# mcb.net
KiCad netlist of a schematic drawn in EAGLE
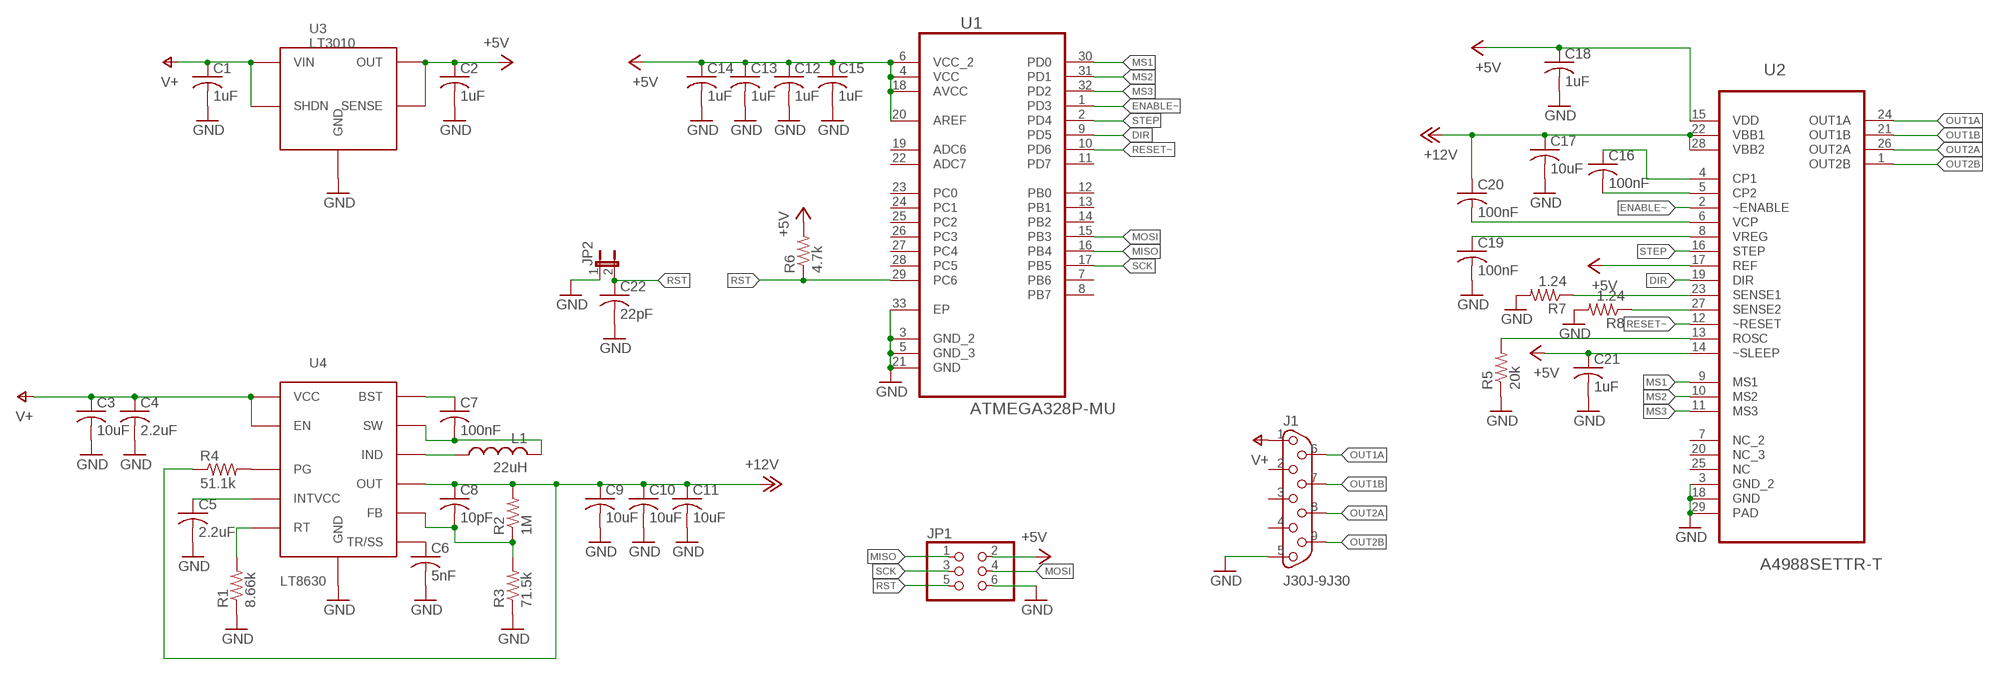
[diagram p0: schematic, sheet 1]

(export (version "E")
  (design (tool "Eeschema 10.0.6"))
  (components
    (comp (ref "C1")
      (value "1uF")
      (footprint "eagle-import:C0603")
      (libsource (lib "eagle-import") (part "C-USC0603"))
    )
    (comp (ref "C2")
      (value "1uF")
      (footprint "eagle-import:C0603")
      (libsource (lib "eagle-import") (part "C-USC0603"))
    )
    (comp (ref "C3")
      (value "10uF")
      (footprint "eagle-import:C1206")
      (libsource (lib "eagle-import") (part "C-USC1206"))
    )
    (comp (ref "C4")
      (value "2.2uF")
      (footprint "eagle-import:C0805")
      (libsource (lib "eagle-import") (part "C-USC0805"))
    )
    (comp (ref "C5")
      (value "2.2uF")
      (footprint "eagle-import:C0805")
      (libsource (lib "eagle-import") (part "C-USC0805"))
    )
    (comp (ref "C6")
      (value "5nF")
      (footprint "eagle-import:C0603")
      (libsource (lib "eagle-import") (part "C-USC0603"))
    )
    (comp (ref "C7")
      (value "100nF")
      (footprint "eagle-import:C0603")
      (libsource (lib "eagle-import") (part "C-USC0603"))
    )
    (comp (ref "C8")
      (value "10pF")
      (footprint "eagle-import:C0603")
      (libsource (lib "eagle-import") (part "C-USC0603"))
    )
    (comp (ref "C9")
      (value "10uF")
      (footprint "eagle-import:C1206")
      (libsource (lib "eagle-import") (part "C-USC1206"))
    )
    (comp (ref "C10")
      (value "10uF")
      (footprint "eagle-import:C1206")
      (libsource (lib "eagle-import") (part "C-USC1206"))
    )
    (comp (ref "C11")
      (value "10uF")
      (footprint "eagle-import:C1206")
      (libsource (lib "eagle-import") (part "C-USC1206"))
    )
    (comp (ref "C12")
      (value "1uF")
      (footprint "eagle-import:C0603")
      (libsource (lib "eagle-import") (part "C-USC0603"))
    )
    (comp (ref "C13")
      (value "1uF")
      (footprint "eagle-import:C0603")
      (libsource (lib "eagle-import") (part "C-USC0603"))
    )
    (comp (ref "C14")
      (value "1uF")
      (footprint "eagle-import:C0603")
      (libsource (lib "eagle-import") (part "C-USC0603"))
    )
    (comp (ref "C15")
      (value "1uF")
      (footprint "eagle-import:C0603")
      (libsource (lib "eagle-import") (part "C-USC0603"))
    )
    (comp (ref "C16")
      (value "100nF")
      (footprint "eagle-import:C0603")
      (libsource (lib "eagle-import") (part "C-USC0603"))
    )
    (comp (ref "C17")
      (value "10uF")
      (footprint "eagle-import:C1206")
      (libsource (lib "eagle-import") (part "C-USC1206"))
    )
    (comp (ref "C18")
      (value "1uF")
      (footprint "eagle-import:C0603")
      (libsource (lib "eagle-import") (part "C-USC0603"))
    )
    (comp (ref "C19")
      (value "100nF")
      (footprint "eagle-import:C0603")
      (libsource (lib "eagle-import") (part "C-USC0603"))
    )
    (comp (ref "C20")
      (value "100nF")
      (footprint "eagle-import:C0603")
      (libsource (lib "eagle-import") (part "C-USC0603"))
    )
    (comp (ref "C21")
      (value "1uF")
      (footprint "eagle-import:C0603")
      (libsource (lib "eagle-import") (part "C-USC0603"))
    )
    (comp (ref "C22")
      (value "22pF")
      (footprint "eagle-import:C0603")
      (libsource (lib "eagle-import") (part "C-USC0603"))
    )
    (comp (ref "J1")
      (value "J30J-9J30")
      (footprint "eagle-import:ZKN-9-J30")
      (libsource (lib "eagle-import") (part "J30J-9J30"))
    )
    (comp (ref "JP1")
      (value "PINHD-2X3")
      (footprint "eagle-import:2X03")
      (libsource (lib "eagle-import") (part "PINHD-2X3"))
    )
    (comp (ref "JP2")
      (value "JUMPER-2SMD-NO")
      (footprint "eagle-import:SJ_2S-NO")
      (libsource (lib "eagle-import") (part "JUMPER-2SMD-NO"))
    )
    (comp (ref "L1")
      (value "22uH")
      (footprint "eagle-import:SRP1265A")
      (libsource (lib "eagle-import") (part "INDUCTOR"))
    )
    (comp (ref "R1")
      (value "8.66k")
      (footprint "eagle-import:R0603")
      (libsource (lib "eagle-import") (part "R-US_R0603"))
    )
    (comp (ref "R2")
      (value "1M")
      (footprint "eagle-import:R0603")
      (libsource (lib "eagle-import") (part "R-US_R0603"))
    )
    (comp (ref "R3")
      (value "71.5k")
      (footprint "eagle-import:R0603")
      (libsource (lib "eagle-import") (part "R-US_R0603"))
    )
    (comp (ref "R4")
      (value "51.1k")
      (footprint "eagle-import:R0603")
      (libsource (lib "eagle-import") (part "R-US_R0603"))
    )
    (comp (ref "R5")
      (value "20k")
      (footprint "eagle-import:R0603")
      (libsource (lib "eagle-import") (part "R-US_R0603"))
    )
    (comp (ref "R6")
      (value "4.7k")
      (footprint "eagle-import:R0603")
      (libsource (lib "eagle-import") (part "R-US_R0603"))
    )
    (comp (ref "R7")
      (value "1.24")
      (footprint "eagle-import:R0603")
      (libsource (lib "eagle-import") (part "R-US_R0603"))
    )
    (comp (ref "R8")
      (value "1.24")
      (footprint "eagle-import:R0603")
      (libsource (lib "eagle-import") (part "R-US_R0603"))
    )
    (comp (ref "U1")
      (value "ATMEGA328P-MU")
      (footprint "eagle-import:QFN50P500X500X100-33N")
      (libsource (lib "eagle-import") (part "ATMEGA328P-MU"))
    )
    (comp (ref "U2")
      (value "A4988SETTR-T")
      (footprint "eagle-import:QFN50P500X500X100-29N")
      (libsource (lib "eagle-import") (part "A4988SETTR-T"))
    )
    (comp (ref "U3")
      (value "LT3010")
      (footprint "eagle-import:8-MSOP")
      (libsource (lib "eagle-import") (part "LT3010"))
    )
    (comp (ref "U4")
      (value "LT8630")
      (footprint "eagle-import:20-TSSOP")
      (libsource (lib "eagle-import") (part "LT8630"))
    )
  )
  (nets
    (net (code "1") (name "+5V") (class "Default")
      (node (ref "C12") (pin "1") (pinfunction "1_1") (pintype "passive"))
      (node (ref "C13") (pin "1") (pinfunction "1_1") (pintype "passive"))
      (node (ref "C14") (pin "1") (pinfunction "1_1") (pintype "passive"))
      (node (ref "C15") (pin "1") (pinfunction "1_1") (pintype "passive"))
      (node (ref "C18") (pin "1") (pinfunction "1_1") (pintype "passive"))
      (node (ref "C2") (pin "1") (pinfunction "1_1") (pintype "passive"))
      (node (ref "C21") (pin "1") (pinfunction "1_1") (pintype "passive"))
      (node (ref "JP1") (pin "2") (pinfunction "2_2") (pintype "passive"))
      (node (ref "R6") (pin "2") (pinfunction "2_2") (pintype "passive"))
      (node (ref "U1") (pin "18") (pinfunction "AVCC_18") (pintype "power_in"))
      (node (ref "U1") (pin "20") (pinfunction "AREF_20") (pintype "input"))
      (node (ref "U1") (pin "4") (pinfunction "VCC_4") (pintype "power_in"))
      (node (ref "U1") (pin "6") (pinfunction "VCC_2_6") (pintype "power_in"))
      (node (ref "U2") (pin "14") (pinfunction "~{SLEEP}_14") (pintype "input"))
      (node (ref "U2") (pin "15") (pinfunction "VDD_15") (pintype "power_in"))
      (node (ref "U2") (pin "17") (pinfunction "REF_17") (pintype "input"))
      (node (ref "U3") (pin "1") (pinfunction "OUT_1") (pintype "bidirectional"))
      (node (ref "U3") (pin "2") (pinfunction "SENSE_2") (pintype "bidirectional"))
    )
    (net (code "2") (name "+12V") (class "Default")
      (node (ref "C10") (pin "1") (pinfunction "1_1") (pintype "passive"))
      (node (ref "C11") (pin "1") (pinfunction "1_1") (pintype "passive"))
      (node (ref "C17") (pin "1") (pinfunction "1_1") (pintype "passive"))
      (node (ref "C20") (pin "1") (pinfunction "1_1") (pintype "passive"))
      (node (ref "C8") (pin "1") (pinfunction "1_1") (pintype "passive"))
      (node (ref "C9") (pin "1") (pinfunction "1_1") (pintype "passive"))
      (node (ref "R2") (pin "2") (pinfunction "2_2") (pintype "passive"))
      (node (ref "R4") (pin "1") (pinfunction "1_1") (pintype "passive"))
      (node (ref "U2") (pin "22") (pinfunction "VBB1_22") (pintype "power_in"))
      (node (ref "U2") (pin "28") (pinfunction "VBB2_28") (pintype "power_in"))
      (node (ref "U4") (pin "P$12") (pinfunction "OUT_P$12") (pintype "bidirectional"))
    )
    (net (code "3") (name "/ENABLE~{}") (class "Default")
      (node (ref "U1") (pin "1") (pinfunction "PD3_1") (pintype "bidirectional"))
      (node (ref "U2") (pin "2") (pinfunction "~{ENABLE}_2") (pintype "input"))
    )
    (net (code "4") (name "/RESET~{}") (class "Default")
      (node (ref "U1") (pin "10") (pinfunction "PD6_10") (pintype "bidirectional"))
      (node (ref "U2") (pin "12") (pinfunction "~{RESET}_12") (pintype "input"))
    )
    (net (code "5") (name "DIR") (class "Default")
      (node (ref "U1") (pin "9") (pinfunction "PD5_9") (pintype "bidirectional"))
      (node (ref "U2") (pin "19") (pinfunction "DIR_19") (pintype "input"))
    )
    (net (code "6") (name "GND") (class "Default")
      (node (ref "C1") (pin "2") (pinfunction "2_2") (pintype "passive"))
      (node (ref "C10") (pin "2") (pinfunction "2_2") (pintype "passive"))
      (node (ref "C11") (pin "2") (pinfunction "2_2") (pintype "passive"))
      (node (ref "C12") (pin "2") (pinfunction "2_2") (pintype "passive"))
      (node (ref "C13") (pin "2") (pinfunction "2_2") (pintype "passive"))
      (node (ref "C14") (pin "2") (pinfunction "2_2") (pintype "passive"))
      (node (ref "C15") (pin "2") (pinfunction "2_2") (pintype "passive"))
      (node (ref "C17") (pin "2") (pinfunction "2_2") (pintype "passive"))
      (node (ref "C18") (pin "2") (pinfunction "2_2") (pintype "passive"))
      (node (ref "C19") (pin "2") (pinfunction "2_2") (pintype "passive"))
      (node (ref "C2") (pin "2") (pinfunction "2_2") (pintype "passive"))
      (node (ref "C21") (pin "2") (pinfunction "2_2") (pintype "passive"))
      (node (ref "C22") (pin "2") (pinfunction "2_2") (pintype "passive"))
      (node (ref "C3") (pin "2") (pinfunction "2_2") (pintype "passive"))
      (node (ref "C4") (pin "2") (pinfunction "2_2") (pintype "passive"))
      (node (ref "C5") (pin "2") (pinfunction "2_2") (pintype "passive"))
      (node (ref "C6") (pin "2") (pinfunction "2_2") (pintype "passive"))
      (node (ref "C9") (pin "2") (pinfunction "2_2") (pintype "passive"))
      (node (ref "J1") (pin "5") (pinfunction "5_5") (pintype "bidirectional"))
      (node (ref "JP1") (pin "6") (pinfunction "6_6") (pintype "passive"))
      (node (ref "JP2") (pin "1") (pinfunction "1_1") (pintype "passive"))
      (node (ref "R1") (pin "1") (pinfunction "1_1") (pintype "passive"))
      (node (ref "R3") (pin "1") (pinfunction "1_1") (pintype "passive"))
      (node (ref "R5") (pin "1") (pinfunction "1_1") (pintype "passive"))
      (node (ref "R7") (pin "2") (pinfunction "2_2") (pintype "passive"))
      (node (ref "R8") (pin "2") (pinfunction "2_2") (pintype "passive"))
      (node (ref "U1") (pin "21") (pinfunction "GND_21") (pintype "passive"))
      (node (ref "U1") (pin "3") (pinfunction "GND_2_3") (pintype "passive"))
      (node (ref "U1") (pin "33") (pinfunction "EP_33") (pintype "passive"))
      (node (ref "U1") (pin "5") (pinfunction "GND_3_5") (pintype "passive"))
      (node (ref "U2") (pin "18") (pinfunction "GND_18") (pintype "passive"))
      (node (ref "U2") (pin "29") (pinfunction "PAD_29") (pintype "passive"))
      (node (ref "U2") (pin "3") (pinfunction "GND_2_3") (pintype "passive"))
      (node (ref "U3") (pin "3") (pinfunction "GND_3") (pintype "bidirectional"))
      (node (ref "U3") (pin "4") (pinfunction "GND_4") (pintype "bidirectional"))
      (node (ref "U3") (pin "6") (pinfunction "GND_6") (pintype "bidirectional"))
      (node (ref "U3") (pin "7") (pinfunction "GND_7") (pintype "bidirectional"))
      (node (ref "U3") (pin "9") (pinfunction "GND_9") (pintype "bidirectional"))
      (node (ref "U4") (pin "P$0") (pinfunction "GND_P$0") (pintype "bidirectional"))
    )
    (net (code "7") (name "MISO") (class "Default")
      (node (ref "JP1") (pin "1") (pinfunction "1_1") (pintype "passive"))
      (node (ref "U1") (pin "16") (pinfunction "PB4_16") (pintype "bidirectional"))
    )
    (net (code "8") (name "MOSI") (class "Default")
      (node (ref "JP1") (pin "4") (pinfunction "4_4") (pintype "passive"))
      (node (ref "U1") (pin "15") (pinfunction "PB3_15") (pintype "bidirectional"))
    )
    (net (code "9") (name "MS1") (class "Default")
      (node (ref "U1") (pin "30") (pinfunction "PD0_30") (pintype "bidirectional"))
      (node (ref "U2") (pin "9") (pinfunction "MS1_9") (pintype "input"))
    )
    (net (code "10") (name "MS2") (class "Default")
      (node (ref "U1") (pin "31") (pinfunction "PD1_31") (pintype "bidirectional"))
      (node (ref "U2") (pin "10") (pinfunction "MS2_10") (pintype "input"))
    )
    (net (code "11") (name "MS3") (class "Default")
      (node (ref "U1") (pin "32") (pinfunction "PD2_32") (pintype "bidirectional"))
      (node (ref "U2") (pin "11") (pinfunction "MS3_11") (pintype "input"))
    )
    (net (code "12") (name "Net-(L1-1)") (class "Default")
      (node (ref "L1") (pin "P$1") (pinfunction "1_P$1") (pintype "passive"))
      (node (ref "U4") (pin "P$14") (pinfunction "IND_P$14") (pintype "bidirectional"))
    )
    (net (code "13") (name "Net-(L1-2)") (class "Default")
      (node (ref "C7") (pin "2") (pinfunction "2_2") (pintype "passive"))
      (node (ref "L1") (pin "P$2") (pinfunction "2_P$2") (pintype "passive"))
      (node (ref "U4") (pin "P$20") (pinfunction "SW_P$20") (pintype "bidirectional"))
    )
    (net (code "14") (name "Net-(U2-CP1)") (class "Default")
      (node (ref "C16") (pin "1") (pinfunction "1_1") (pintype "passive"))
      (node (ref "U2") (pin "4") (pinfunction "CP1_4") (pintype "passive"))
    )
    (net (code "15") (name "Net-(U2-CP2)") (class "Default")
      (node (ref "C16") (pin "2") (pinfunction "2_2") (pintype "passive"))
      (node (ref "U2") (pin "5") (pinfunction "CP2_5") (pintype "passive"))
    )
    (net (code "16") (name "Net-(U2-ROSC)") (class "Default")
      (node (ref "R5") (pin "2") (pinfunction "2_2") (pintype "passive"))
      (node (ref "U2") (pin "13") (pinfunction "ROSC_13") (pintype "input"))
    )
    (net (code "17") (name "Net-(U2-SENSE1)") (class "Default")
      (node (ref "R7") (pin "1") (pinfunction "1_1") (pintype "passive"))
      (node (ref "U2") (pin "23") (pinfunction "SENSE1_23") (pintype "input"))
    )
    (net (code "18") (name "Net-(U2-SENSE2)") (class "Default")
      (node (ref "R8") (pin "1") (pinfunction "1_1") (pintype "passive"))
      (node (ref "U2") (pin "27") (pinfunction "SENSE2_27") (pintype "input"))
    )
    (net (code "19") (name "Net-(U2-VCP)") (class "Default")
      (node (ref "C20") (pin "2") (pinfunction "2_2") (pintype "passive"))
      (node (ref "U2") (pin "6") (pinfunction "VCP_6") (pintype "passive"))
    )
    (net (code "20") (name "Net-(U2-VREG)") (class "Default")
      (node (ref "C19") (pin "1") (pinfunction "1_1") (pintype "passive"))
      (node (ref "U2") (pin "8") (pinfunction "VREG_8") (pintype "passive"))
    )
    (net (code "21") (name "Net-(U4-BST)") (class "Default")
      (node (ref "C7") (pin "1") (pinfunction "1_1") (pintype "passive"))
      (node (ref "U4") (pin "P$18") (pinfunction "BST_P$18") (pintype "bidirectional"))
    )
    (net (code "22") (name "Net-(U4-FB)") (class "Default")
      (node (ref "C8") (pin "2") (pinfunction "2_2") (pintype "passive"))
      (node (ref "R2") (pin "1") (pinfunction "1_1") (pintype "passive"))
      (node (ref "R3") (pin "2") (pinfunction "2_2") (pintype "passive"))
      (node (ref "U4") (pin "P$11") (pinfunction "FB_P$11") (pintype "bidirectional"))
    )
    (net (code "23") (name "Net-(U4-INTVCC)") (class "Default")
      (node (ref "C5") (pin "1") (pinfunction "1_1") (pintype "passive"))
      (node (ref "U4") (pin "P$16") (pinfunction "INTVCC_P$16") (pintype "bidirectional"))
    )
    (net (code "24") (name "Net-(U4-PG)") (class "Default")
      (node (ref "R4") (pin "2") (pinfunction "2_2") (pintype "passive"))
      (node (ref "U4") (pin "P$5") (pinfunction "PG_P$5") (pintype "bidirectional"))
    )
    (net (code "25") (name "Net-(U4-RT)") (class "Default")
      (node (ref "R1") (pin "2") (pinfunction "2_2") (pintype "passive"))
      (node (ref "U4") (pin "P$8") (pinfunction "RT_P$8") (pintype "bidirectional"))
    )
    (net (code "26") (name "Net-(U4-TR{slash}SS)") (class "Default")
      (node (ref "C6") (pin "1") (pinfunction "1_1") (pintype "passive"))
      (node (ref "U4") (pin "P$10") (pinfunction "TR/SS_P$10") (pintype "bidirectional"))
    )
    (net (code "27") (name "OUT1A") (class "Default")
      (node (ref "J1") (pin "6") (pinfunction "6_6") (pintype "bidirectional"))
      (node (ref "U2") (pin "24") (pinfunction "OUT1A_24") (pintype "output"))
    )
    (net (code "28") (name "OUT1B") (class "Default")
      (node (ref "J1") (pin "7") (pinfunction "7_7") (pintype "bidirectional"))
      (node (ref "U2") (pin "21") (pinfunction "OUT1B_21") (pintype "output"))
    )
    (net (code "29") (name "OUT2A") (class "Default")
      (node (ref "J1") (pin "8") (pinfunction "8_8") (pintype "bidirectional"))
      (node (ref "U2") (pin "26") (pinfunction "OUT2A_26") (pintype "output"))
    )
    (net (code "30") (name "OUT2B") (class "Default")
      (node (ref "J1") (pin "9") (pinfunction "9_9") (pintype "bidirectional"))
      (node (ref "U2") (pin "1") (pinfunction "OUT2B_1") (pintype "output"))
    )
    (net (code "31") (name "RST") (class "Default")
      (node (ref "C22") (pin "1") (pinfunction "1_1") (pintype "passive"))
      (node (ref "JP1") (pin "5") (pinfunction "5_5") (pintype "passive"))
      (node (ref "JP2") (pin "2") (pinfunction "2_2") (pintype "passive"))
      (node (ref "R6") (pin "1") (pinfunction "1_1") (pintype "passive"))
      (node (ref "U1") (pin "29") (pinfunction "PC6_29") (pintype "bidirectional"))
    )
    (net (code "32") (name "SCK") (class "Default")
      (node (ref "JP1") (pin "3") (pinfunction "3_3") (pintype "passive"))
      (node (ref "U1") (pin "17") (pinfunction "PB5_17") (pintype "bidirectional"))
    )
    (net (code "33") (name "STEP") (class "Default")
      (node (ref "U1") (pin "2") (pinfunction "PD4_2") (pintype "bidirectional"))
      (node (ref "U2") (pin "16") (pinfunction "STEP_16") (pintype "input"))
    )
    (net (code "34") (name "V+") (class "Default")
      (node (ref "C1") (pin "1") (pinfunction "1_1") (pintype "passive"))
      (node (ref "C3") (pin "1") (pinfunction "1_1") (pintype "passive"))
      (node (ref "C4") (pin "1") (pinfunction "1_1") (pintype "passive"))
      (node (ref "J1") (pin "1") (pinfunction "1_1") (pintype "bidirectional"))
      (node (ref "U3") (pin "5") (pinfunction "SHDN_5") (pintype "bidirectional"))
      (node (ref "U3") (pin "8") (pinfunction "VIN_8") (pintype "bidirectional"))
      (node (ref "U4") (pin "P$1") (pinfunction "VCC_P$1") (pintype "bidirectional"))
      (node (ref "U4") (pin "P$3") (pinfunction "EN_P$3") (pintype "bidirectional"))
    )
    (net (code "35") (name "unconnected-(J1-Pad2)") (class "Default")
      (node (ref "J1") (pin "2") (pinfunction "2_2") (pintype "bidirectional"))
    )
    (net (code "36") (name "unconnected-(J1-Pad3)") (class "Default")
      (node (ref "J1") (pin "3") (pinfunction "3_3") (pintype "bidirectional"))
    )
    (net (code "37") (name "unconnected-(J1-Pad4)") (class "Default")
      (node (ref "J1") (pin "4") (pinfunction "4_4") (pintype "bidirectional"))
    )
    (net (code "38") (name "unconnected-(U1-ADC6-Pad19)") (class "Default")
      (node (ref "U1") (pin "19") (pinfunction "ADC6_19") (pintype "input"))
    )
    (net (code "39") (name "unconnected-(U1-ADC7-Pad22)") (class "Default")
      (node (ref "U1") (pin "22") (pinfunction "ADC7_22") (pintype "input"))
    )
    (net (code "40") (name "unconnected-(U1-PB0-Pad12)") (class "Default")
      (node (ref "U1") (pin "12") (pinfunction "PB0_12") (pintype "bidirectional"))
    )
    (net (code "41") (name "unconnected-(U1-PB1-Pad13)") (class "Default")
      (node (ref "U1") (pin "13") (pinfunction "PB1_13") (pintype "bidirectional"))
    )
    (net (code "42") (name "unconnected-(U1-PB2-Pad14)") (class "Default")
      (node (ref "U1") (pin "14") (pinfunction "PB2_14") (pintype "bidirectional"))
    )
    (net (code "43") (name "unconnected-(U1-PB6-Pad7)") (class "Default")
      (node (ref "U1") (pin "7") (pinfunction "PB6_7") (pintype "bidirectional"))
    )
    (net (code "44") (name "unconnected-(U1-PB7-Pad8)") (class "Default")
      (node (ref "U1") (pin "8") (pinfunction "PB7_8") (pintype "bidirectional"))
    )
    (net (code "45") (name "unconnected-(U1-PC0-Pad23)") (class "Default")
      (node (ref "U1") (pin "23") (pinfunction "PC0_23") (pintype "bidirectional"))
    )
    (net (code "46") (name "unconnected-(U1-PC1-Pad24)") (class "Default")
      (node (ref "U1") (pin "24") (pinfunction "PC1_24") (pintype "bidirectional"))
    )
    (net (code "47") (name "unconnected-(U1-PC2-Pad25)") (class "Default")
      (node (ref "U1") (pin "25") (pinfunction "PC2_25") (pintype "bidirectional"))
    )
    (net (code "48") (name "unconnected-(U1-PC3-Pad26)") (class "Default")
      (node (ref "U1") (pin "26") (pinfunction "PC3_26") (pintype "bidirectional"))
    )
    (net (code "49") (name "unconnected-(U1-PC4-Pad27)") (class "Default")
      (node (ref "U1") (pin "27") (pinfunction "PC4_27") (pintype "bidirectional"))
    )
    (net (code "50") (name "unconnected-(U1-PC5-Pad28)") (class "Default")
      (node (ref "U1") (pin "28") (pinfunction "PC5_28") (pintype "bidirectional"))
    )
    (net (code "51") (name "unconnected-(U1-PD7-Pad11)") (class "Default")
      (node (ref "U1") (pin "11") (pinfunction "PD7_11") (pintype "bidirectional"))
    )
    (net (code "52") (name "unconnected-(U2-NC-Pad25)") (class "Default")
      (node (ref "U2") (pin "25") (pinfunction "NC_25") (pintype "no_connect"))
    )
    (net (code "53") (name "unconnected-(U2-NC_2-Pad7)") (class "Default")
      (node (ref "U2") (pin "7") (pinfunction "NC_2_7") (pintype "no_connect"))
    )
    (net (code "54") (name "unconnected-(U2-NC_3-Pad20)") (class "Default")
      (node (ref "U2") (pin "20") (pinfunction "NC_3_20") (pintype "no_connect"))
    )
  )
)
